# e407-eth-jack-replacment.net
KiCad netlist of a schematic drawn in EAGLE
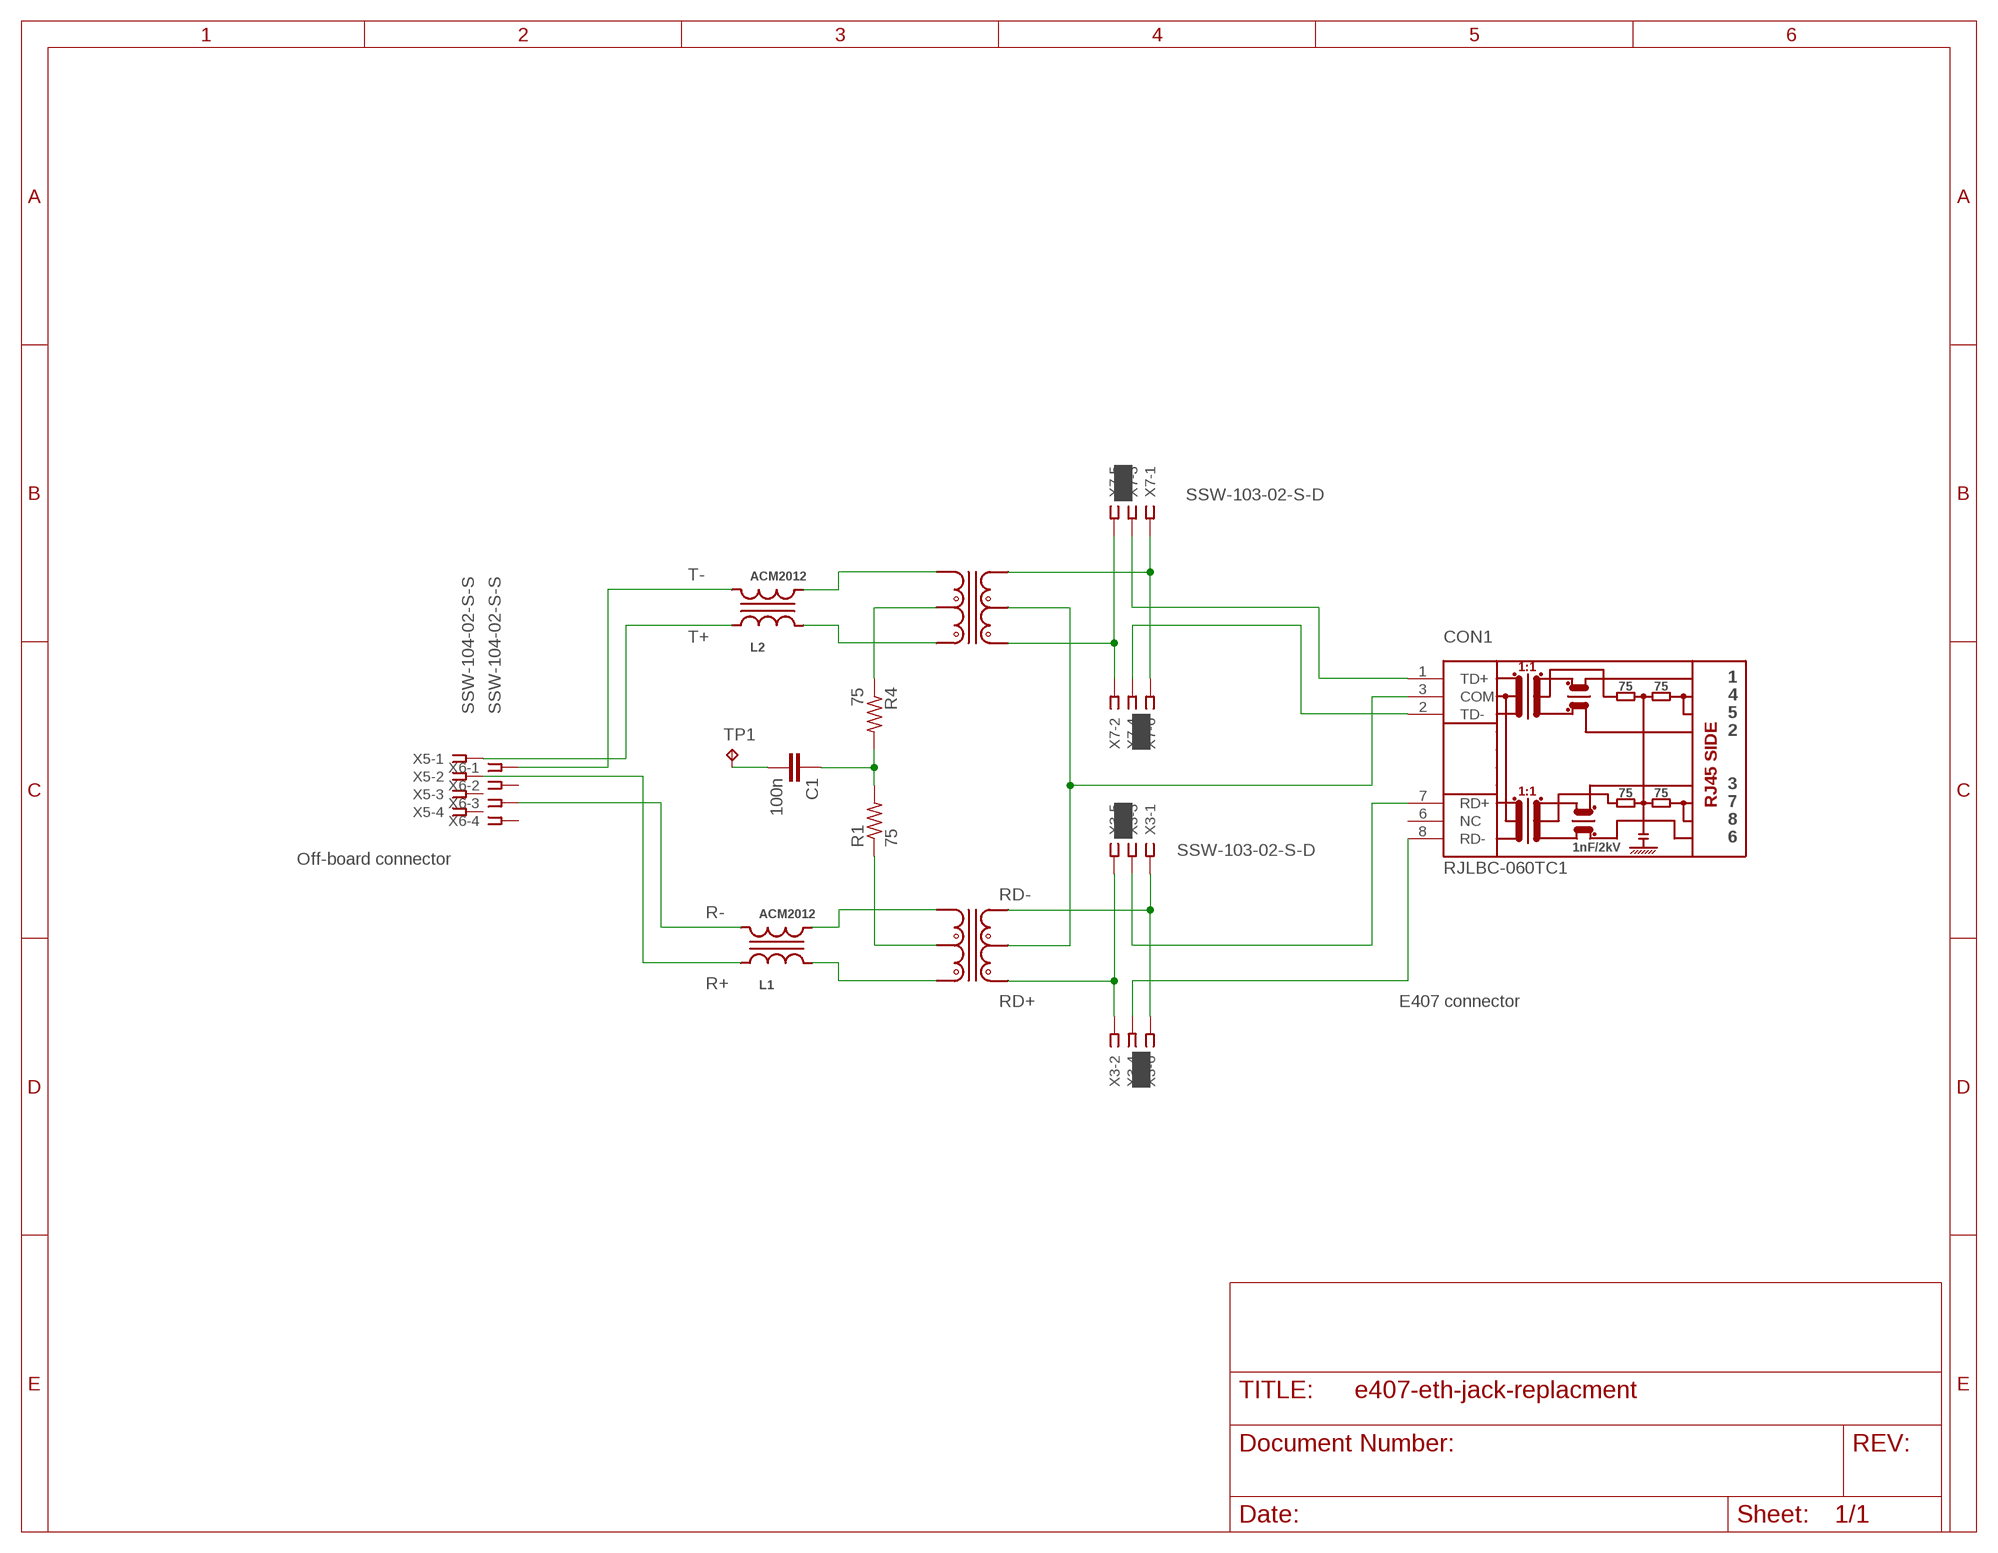
[diagram p0: schematic, sheet 1]

(export (version "E")
  (design (tool "Eeschema 10.0.6"))
  (components
    (comp (ref "C1")
      (value "100n")
      (footprint "eagle-import:0603-B-NOSILK")
      (libsource (lib "eagle-import") (part "C-EU0603-B-NOSILK"))
    )
    (comp (ref "CON1")
      (value "RJLBC-060TC1")
      (footprint "eagle-import:RJLBC-060TC1")
      (libsource (lib "eagle-import") (part "RJLBC-060TC1"))
    )
    (comp (ref "L1")
      (value "ACM2012")
      (footprint "eagle-import:TDK-ACM2012")
      (libsource (lib "eagle-import") (part "ACM2012"))
    )
    (comp (ref "L2")
      (value "ACM2012")
      (footprint "eagle-import:TDK-ACM2012")
      (libsource (lib "eagle-import") (part "ACM2012"))
    )
    (comp (ref "R1")
      (value "75")
      (footprint "eagle-import:0603-B-NOSILK")
      (libsource (lib "eagle-import") (part "R-US_0603-B-NOSILK"))
    )
    (comp (ref "R4")
      (value "75")
      (footprint "eagle-import:0603-B-NOSILK")
      (libsource (lib "eagle-import") (part "R-US_0603-B-NOSILK"))
    )
    (comp (ref "T1")
      (value "ALT4532")
      (footprint "eagle-import:TDK-ALT4532")
      (libsource (lib "eagle-import") (part "ALT4532"))
    )
    (comp (ref "T2")
      (value "ALT4532")
      (footprint "eagle-import:TDK-ALT4532")
      (libsource (lib "eagle-import") (part "ALT4532"))
    )
    (comp (ref "TP1")
      (value "TPPAD1-13")
      (footprint "eagle-import:P1-13")
      (libsource (lib "eagle-import") (part "TPPAD1-13"))
    )
    (comp (ref "X3")
      (value "SSW-103-02-S-D")
      (footprint "eagle-import:SSW-103-02-S-D")
      (libsource (lib "eagle-import") (part "SSW-103-02-S-D"))
    )
    (comp (ref "X5")
      (value "SSW-104-02-S-S")
      (footprint "eagle-import:SSW-104-02-S-S")
      (libsource (lib "eagle-import") (part "SSW-104-02-S-S"))
    )
    (comp (ref "X6")
      (value "SSW-104-02-S-S")
      (footprint "eagle-import:SSW-104-02-S-S")
      (libsource (lib "eagle-import") (part "SSW-104-02-S-S"))
    )
    (comp (ref "X7")
      (value "SSW-103-02-S-D")
      (footprint "eagle-import:SSW-103-02-S-D")
      (libsource (lib "eagle-import") (part "SSW-103-02-S-D"))
    )
  )
  (nets
    (net (code "1") (name "Net-(C1-Pad1)") (class "Default")
      (node (ref "C1") (pin "1") (pinfunction "1_1") (pintype "passive"))
      (node (ref "R1") (pin "2") (pinfunction "2_2") (pintype "passive"))
      (node (ref "R4") (pin "2") (pinfunction "2_2") (pintype "passive"))
    )
    (net (code "2") (name "Net-(C1-Pad2)") (class "Default")
      (node (ref "C1") (pin "2") (pinfunction "2_2") (pintype "passive"))
      (node (ref "TP1") (pin "TP") (pinfunction "TP_TP") (pintype "input"))
    )
    (net (code "3") (name "Net-(CON1-COM)") (class "Default")
      (node (ref "CON1") (pin "3") (pinfunction "COM_3") (pintype "bidirectional"))
      (node (ref "T1") (pin "6") (pinfunction "6_6") (pintype "passive"))
      (node (ref "T2") (pin "6") (pinfunction "6_6") (pintype "passive"))
    )
    (net (code "4") (name "Net-(CON1-RD+)") (class "Default")
      (node (ref "CON1") (pin "7") (pinfunction "RD+_7") (pintype "bidirectional"))
      (node (ref "X3") (pin "3") (pinfunction "1_3") (pintype "passive"))
    )
    (net (code "5") (name "Net-(CON1-RD-)") (class "Default")
      (node (ref "CON1") (pin "8") (pinfunction "RD-_8") (pintype "bidirectional"))
      (node (ref "X3") (pin "4") (pinfunction "1_4") (pintype "passive"))
    )
    (net (code "6") (name "Net-(CON1-TD+)") (class "Default")
      (node (ref "CON1") (pin "1") (pinfunction "TD+_1") (pintype "bidirectional"))
      (node (ref "X7") (pin "3") (pinfunction "1_3") (pintype "passive"))
    )
    (net (code "7") (name "Net-(CON1-TD-)") (class "Default")
      (node (ref "CON1") (pin "2") (pinfunction "TD-_2") (pintype "bidirectional"))
      (node (ref "X7") (pin "4") (pinfunction "1_4") (pintype "passive"))
    )
    (net (code "8") (name "Net-(L1-Pad3)") (class "Default")
      (node (ref "L1") (pin "3") (pinfunction "3_3") (pintype "passive"))
      (node (ref "T1") (pin "4") (pinfunction "4_4") (pintype "passive"))
    )
    (net (code "9") (name "Net-(L1-Pad4)") (class "Default")
      (node (ref "L1") (pin "4") (pinfunction "4_4") (pintype "passive"))
      (node (ref "T1") (pin "5") (pinfunction "5_5") (pintype "passive"))
    )
    (net (code "10") (name "Net-(L2-Pad1)") (class "Default")
      (node (ref "L2") (pin "1") (pinfunction "1_1") (pintype "passive"))
      (node (ref "X5") (pin "1") (pinfunction "1_1") (pintype "passive"))
    )
    (net (code "11") (name "Net-(L2-Pad2)") (class "Default")
      (node (ref "L2") (pin "2") (pinfunction "2_2") (pintype "passive"))
      (node (ref "X6") (pin "1") (pinfunction "1_1") (pintype "passive"))
    )
    (net (code "12") (name "Net-(L2-Pad3)") (class "Default")
      (node (ref "L2") (pin "3") (pinfunction "3_3") (pintype "passive"))
      (node (ref "T2") (pin "4") (pinfunction "4_4") (pintype "passive"))
    )
    (net (code "13") (name "Net-(L2-Pad4)") (class "Default")
      (node (ref "L2") (pin "4") (pinfunction "4_4") (pintype "passive"))
      (node (ref "T2") (pin "5") (pinfunction "5_5") (pintype "passive"))
    )
    (net (code "14") (name "Net-(R1-Pad1)") (class "Default")
      (node (ref "R1") (pin "1") (pinfunction "1_1") (pintype "passive"))
      (node (ref "T1") (pin "3") (pinfunction "3_3") (pintype "passive"))
    )
    (net (code "15") (name "Net-(R4-Pad1)") (class "Default")
      (node (ref "R4") (pin "1") (pinfunction "1_1") (pintype "passive"))
      (node (ref "T2") (pin "3") (pinfunction "3_3") (pintype "passive"))
    )
    (net (code "16") (name "Net-(X3B-1)") (class "Default")
      (node (ref "T1") (pin "1") (pinfunction "1_1") (pintype "passive"))
      (node (ref "X3") (pin "2") (pinfunction "1_2") (pintype "passive"))
      (node (ref "X3") (pin "5") (pinfunction "1_5") (pintype "passive"))
    )
    (net (code "17") (name "Net-(X3F-1)") (class "Default")
      (node (ref "T1") (pin "2") (pinfunction "2_2") (pintype "passive"))
      (node (ref "X3") (pin "1") (pinfunction "1_1") (pintype "passive"))
      (node (ref "X3") (pin "6") (pinfunction "1_6") (pintype "passive"))
    )
    (net (code "18") (name "Net-(X5B-1)") (class "Default")
      (node (ref "L1") (pin "1") (pinfunction "1_1") (pintype "passive"))
      (node (ref "X5") (pin "2") (pinfunction "1_2") (pintype "passive"))
    )
    (net (code "19") (name "Net-(X6C-1)") (class "Default")
      (node (ref "L1") (pin "2") (pinfunction "2_2") (pintype "passive"))
      (node (ref "X6") (pin "3") (pinfunction "1_3") (pintype "passive"))
    )
    (net (code "20") (name "Net-(X7B-1)") (class "Default")
      (node (ref "T2") (pin "1") (pinfunction "1_1") (pintype "passive"))
      (node (ref "X7") (pin "2") (pinfunction "1_2") (pintype "passive"))
      (node (ref "X7") (pin "5") (pinfunction "1_5") (pintype "passive"))
    )
    (net (code "21") (name "Net-(X7F-1)") (class "Default")
      (node (ref "T2") (pin "2") (pinfunction "2_2") (pintype "passive"))
      (node (ref "X7") (pin "1") (pinfunction "1_1") (pintype "passive"))
      (node (ref "X7") (pin "6") (pinfunction "1_6") (pintype "passive"))
    )
    (net (code "22") (name "unconnected-(CON1-NC-Pad6)") (class "Default")
      (node (ref "CON1") (pin "6") (pinfunction "NC_6") (pintype "bidirectional"))
    )
    (net (code "23") (name "unconnected-(X5C-1-Pad3)") (class "Default")
      (node (ref "X5") (pin "3") (pinfunction "1_3") (pintype "passive"))
    )
    (net (code "24") (name "unconnected-(X5D-1-Pad4)") (class "Default")
      (node (ref "X5") (pin "4") (pinfunction "1_4") (pintype "passive"))
    )
    (net (code "25") (name "unconnected-(X6B-1-Pad2)") (class "Default")
      (node (ref "X6") (pin "2") (pinfunction "1_2") (pintype "passive"))
    )
    (net (code "26") (name "unconnected-(X6D-1-Pad4)") (class "Default")
      (node (ref "X6") (pin "4") (pinfunction "1_4") (pintype "passive"))
    )
  )
)
